# Main.net
KiCad netlist of a schematic drawn in Altium Designer
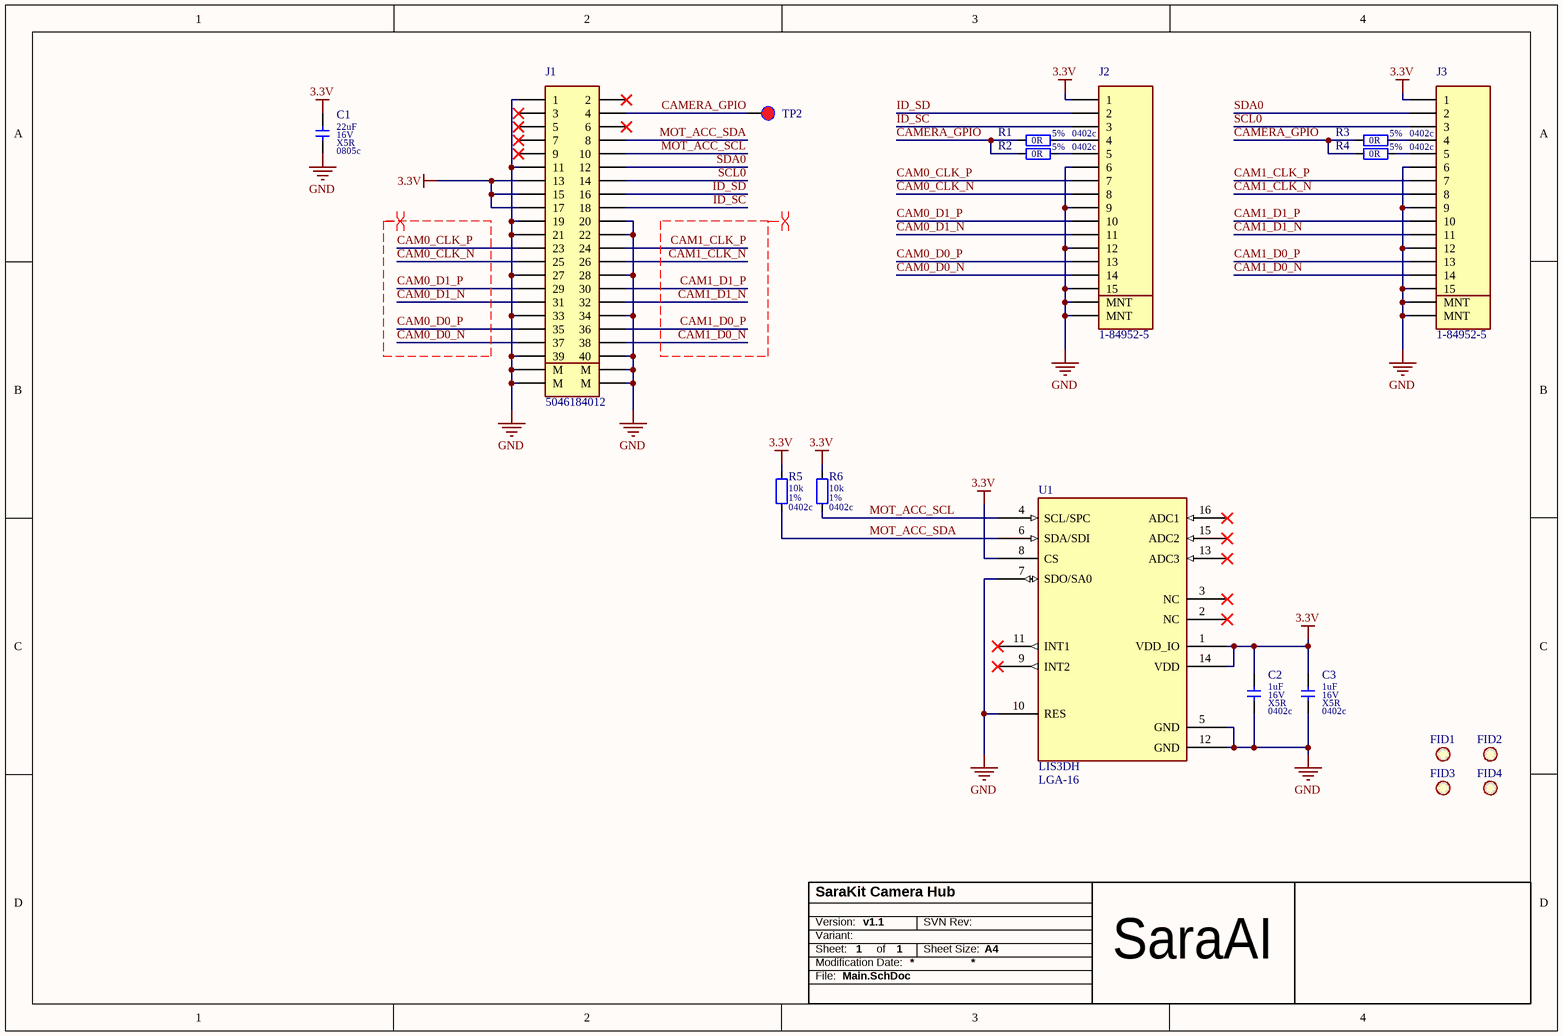
[diagram p0: Main.SchDoc]

(export (version "E")
  (design (tool "Eeschema 10.0.6"))
  (components
    (comp (ref "C1")
      (value "CL21A226MOQNNNE")
      (footprint "CAPC2013X145L")
      (description "SMT 0805c 22uF 16V 20% X5R 1.6MHz 85'C")
      (fields
        (field (name "11 PARAMETER 4") "X5R")
        (field (name "07 PACKAGE") "0805c")
        (field (name "08 PARAMETER 1") "22uF")
        (field (name "09 PARAMETER 2") "16V")
      )
      (libsource (lib "MS_Altium_Lib") (part "CAPACITOR"))
    )
    (comp (ref "C2")
      (value "CL05A105KO5NNNC")
      (footprint "CAPC1005X60L")
      (description "SMT 0402c 1uF 16V 10% X5R 11.9MHz 85'C")
      (fields
        (field (name "11 PARAMETER 4") "X5R")
        (field (name "07 PACKAGE") "0402c")
        (field (name "08 PARAMETER 1") "1uF")
        (field (name "09 PARAMETER 2") "16V")
      )
      (libsource (lib "MS_Altium_Lib") (part "CAPACITOR"))
    )
    (comp (ref "C3")
      (value "CL05A105KO5NNNC")
      (footprint "CAPC1005X60L")
      (description "SMT 0402c 1uF 16V 10% X5R 11.9MHz 85'C")
      (fields
        (field (name "11 PARAMETER 4") "X5R")
        (field (name "07 PACKAGE") "0402c")
        (field (name "08 PARAMETER 1") "1uF")
        (field (name "09 PARAMETER 2") "16V")
      )
      (libsource (lib "MS_Altium_Lib") (part "CAPACITOR"))
    )
    (comp (ref "FID1")
      (value "FIDUCIAL")
      (footprint "FIDUCIAL 2MM")
      (libsource (lib "MS_Altium_Lib") (part "FIDUCIAL"))
    )
    (comp (ref "FID2")
      (value "FIDUCIAL")
      (footprint "FIDUCIAL 2MM")
      (libsource (lib "MS_Altium_Lib") (part "FIDUCIAL"))
    )
    (comp (ref "FID3")
      (value "FIDUCIAL")
      (footprint "FIDUCIAL 2MM")
      (libsource (lib "MS_Altium_Lib") (part "FIDUCIAL"))
    )
    (comp (ref "FID4")
      (value "FIDUCIAL")
      (footprint "FIDUCIAL 2MM")
      (libsource (lib "MS_Altium_Lib") (part "FIDUCIAL"))
    )
    (comp (ref "J1")
      (value "5046184012")
      (footprint "MOLEX 5046184012")
      (description "SMT 2x20 0.35mm Straight 50V 0.3A")
      (fields (field (name "02 MPN") "5046184012"))
      (libsource (lib "MS_Altium_Lib") (part "CONNECTOR 2X22 4MNT ODDEVEN"))
    )
    (comp (ref "J2")
      (value "1-84952-5")
      (footprint "TE 1-84952-5")
      (description "SMT 1x15 1mm Bottom Contact Right Angle 200VAC 1A")
      (fields (field (name "02 MPN") "1-84952-5"))
      (libsource (lib "MS_Altium_Lib") (part "CONNECTOR 1X15 2MNT"))
    )
    (comp (ref "J3")
      (value "1-84952-5")
      (footprint "TE 1-84952-5")
      (description "SMT 1x15 1mm Bottom Contact Right Angle 200VAC 1A")
      (fields (field (name "02 MPN") "1-84952-5"))
      (libsource (lib "MS_Altium_Lib") (part "CONNECTOR 1X15 2MNT"))
    )
    (comp (ref "R1")
      (value "RC0402JR-070RL")
      (footprint "RESC1005X40L")
      (description "SMT 0402c 0R 5% 62.5mW 200ppm/K 50V")
      (fields
        (field (name "07 PACKAGE") "0402c")
        (field (name "09 PARAMETER 2") "5%")
        (field (name "08 PARAMETER 1") "0R")
      )
      (libsource (lib "MS_Altium_Lib") (part "RESISTOR"))
    )
    (comp (ref "R2")
      (value "RC0402JR-070RL")
      (footprint "RESC1005X40L")
      (description "SMT 0402c 0R 5% 62.5mW 200ppm/K 50V")
      (fields
        (field (name "07 PACKAGE") "0402c")
        (field (name "09 PARAMETER 2") "5%")
        (field (name "08 PARAMETER 1") "0R")
      )
      (libsource (lib "MS_Altium_Lib") (part "RESISTOR"))
    )
    (comp (ref "R3")
      (value "RC0402JR-070RL")
      (footprint "RESC1005X40L")
      (description "SMT 0402c 0R 5% 62.5mW 200ppm/K 50V")
      (fields
        (field (name "07 PACKAGE") "0402c")
        (field (name "09 PARAMETER 2") "5%")
        (field (name "08 PARAMETER 1") "0R")
      )
      (libsource (lib "MS_Altium_Lib") (part "RESISTOR"))
    )
    (comp (ref "R4")
      (value "RC0402JR-070RL")
      (footprint "RESC1005X40L")
      (description "SMT 0402c 0R 5% 62.5mW 200ppm/K 50V")
      (fields
        (field (name "07 PACKAGE") "0402c")
        (field (name "09 PARAMETER 2") "5%")
        (field (name "08 PARAMETER 1") "0R")
      )
      (libsource (lib "MS_Altium_Lib") (part "RESISTOR"))
    )
    (comp (ref "R5")
      (value "RC0402FR-0710KL")
      (footprint "RESC1005X40L")
      (description "SMT 0402c 10k 1% 62.5mW 100ppm/K 50V")
      (fields
        (field (name "07 PACKAGE") "0402c")
        (field (name "09 PARAMETER 2") "1%")
        (field (name "08 PARAMETER 1") "10k")
      )
      (libsource (lib "") (part "RESISTOR_1"))
    )
    (comp (ref "R6")
      (value "RC0402FR-0710KL")
      (footprint "RESC1005X40L")
      (description "SMT 0402c 10k 1% 62.5mW 100ppm/K 50V")
      (fields
        (field (name "07 PACKAGE") "0402c")
        (field (name "09 PARAMETER 2") "1%")
        (field (name "08 PARAMETER 1") "10k")
      )
      (libsource (lib "") (part "RESISTOR_1"))
    )
    (comp (ref "TP2")
      (value "TESTPAD")
      (footprint "TP 1.5mm")
      (libsource (lib "MS_Altium_Lib") (part "TESTPAD"))
    )
    (comp (ref "U1")
      (value "LIS3DH")
      (footprint "LGA16R50P5X3_300X300X100")
      (description "SMT LGA-16 ACCELEROMETER 1.71V - 3.6V +/- 16g")
      (fields (field (name "02 MPN") "LIS3DH") (field (name "07 PACKAGE") "LGA-16"))
      (libsource (lib "MS_Altium_Lib") (part "LIS3DH"))
    )
  )
  (nets
    (net (code "2") (name "/CAM0_CLK_N") (class "Default")
      (node (ref "J1") (pin "25") (pinfunction "25_25") (pintype "passive"))
      (node (ref "J2") (pin "8") (pinfunction "8_8") (pintype "passive"))
    )
    (net (code "3") (name "/CAM0_CLK_P") (class "Default")
      (node (ref "J1") (pin "23") (pinfunction "23_23") (pintype "passive"))
      (node (ref "J2") (pin "7") (pinfunction "7_7") (pintype "passive"))
    )
    (net (code "4") (name "/CAM0_D0_N") (class "Default")
      (node (ref "J1") (pin "37") (pinfunction "37_37") (pintype "passive"))
      (node (ref "J2") (pin "14") (pinfunction "14_14") (pintype "passive"))
    )
    (net (code "5") (name "/CAM0_D0_P") (class "Default")
      (node (ref "J1") (pin "35") (pinfunction "35_35") (pintype "passive"))
      (node (ref "J2") (pin "13") (pinfunction "13_13") (pintype "passive"))
    )
    (net (code "6") (name "/CAM0_D1_N") (class "Default")
      (node (ref "J1") (pin "31") (pinfunction "31_31") (pintype "passive"))
      (node (ref "J2") (pin "11") (pinfunction "11_11") (pintype "passive"))
    )
    (net (code "7") (name "/CAM0_D1_P") (class "Default")
      (node (ref "J1") (pin "29") (pinfunction "29_29") (pintype "passive"))
      (node (ref "J2") (pin "10") (pinfunction "10_10") (pintype "passive"))
    )
    (net (code "8") (name "/CAM1_CLK_N") (class "Default")
      (node (ref "J1") (pin "26") (pinfunction "26_26") (pintype "passive"))
      (node (ref "J3") (pin "8") (pinfunction "8_8") (pintype "passive"))
    )
    (net (code "9") (name "/CAM1_CLK_P") (class "Default")
      (node (ref "J1") (pin "24") (pinfunction "24_24") (pintype "passive"))
      (node (ref "J3") (pin "7") (pinfunction "7_7") (pintype "passive"))
    )
    (net (code "10") (name "/CAM1_D0_N") (class "Default")
      (node (ref "J1") (pin "38") (pinfunction "38_38") (pintype "passive"))
      (node (ref "J3") (pin "14") (pinfunction "14_14") (pintype "passive"))
    )
    (net (code "11") (name "/CAM1_D0_P") (class "Default")
      (node (ref "J1") (pin "36") (pinfunction "36_36") (pintype "passive"))
      (node (ref "J3") (pin "13") (pinfunction "13_13") (pintype "passive"))
    )
    (net (code "12") (name "/CAM1_D1_N") (class "Default")
      (node (ref "J1") (pin "32") (pinfunction "32_32") (pintype "passive"))
      (node (ref "J3") (pin "11") (pinfunction "11_11") (pintype "passive"))
    )
    (net (code "13") (name "/CAM1_D1_P") (class "Default")
      (node (ref "J1") (pin "30") (pinfunction "30_30") (pintype "passive"))
      (node (ref "J3") (pin "10") (pinfunction "10_10") (pintype "passive"))
    )
    (net (code "14") (name "/CAMERA_GPIO") (class "Default")
      (node (ref "J1") (pin "4") (pinfunction "4_4") (pintype "passive"))
      (node (ref "R1") (pin "1") (pinfunction "1_1") (pintype "passive"))
      (node (ref "R2") (pin "1") (pinfunction "1_1") (pintype "passive"))
      (node (ref "R3") (pin "1") (pinfunction "1_1") (pintype "passive"))
      (node (ref "R4") (pin "1") (pinfunction "1_1") (pintype "passive"))
      (node (ref "TP2") (pin "1") (pinfunction "1_1") (pintype "passive"))
    )
    (net (code "15") (name "/ID_SC") (class "Default")
      (node (ref "J1") (pin "18") (pinfunction "18_18") (pintype "passive"))
      (node (ref "J2") (pin "3") (pinfunction "3_3") (pintype "passive"))
    )
    (net (code "16") (name "/ID_SD") (class "Default")
      (node (ref "J1") (pin "16") (pinfunction "16_16") (pintype "passive"))
      (node (ref "J2") (pin "2") (pinfunction "2_2") (pintype "passive"))
    )
    (net (code "17") (name "/MOT_ACC_SCL") (class "Default")
      (node (ref "J1") (pin "10") (pinfunction "10_10") (pintype "passive"))
      (node (ref "R6") (pin "1") (pinfunction "1_1") (pintype "passive"))
      (node (ref "U1") (pin "4") (pinfunction "SCL/SPC_4") (pintype "input"))
    )
    (net (code "18") (name "/MOT_ACC_SDA") (class "Default")
      (node (ref "J1") (pin "8") (pinfunction "8_8") (pintype "passive"))
      (node (ref "R5") (pin "1") (pinfunction "1_1") (pintype "passive"))
      (node (ref "U1") (pin "6") (pinfunction "SDA/SDI_6") (pintype "input"))
    )
    (net (code "19") (name "/SCL0") (class "Default")
      (node (ref "J1") (pin "14") (pinfunction "14_14") (pintype "passive"))
      (node (ref "J3") (pin "3") (pinfunction "3_3") (pintype "passive"))
    )
    (net (code "20") (name "/SDA0") (class "Default")
      (node (ref "J1") (pin "12") (pinfunction "12_12") (pintype "passive"))
      (node (ref "J3") (pin "2") (pinfunction "2_2") (pintype "passive"))
    )
    (net (code "21") (name "3.3V") (class "Default")
      (node (ref "C1") (pin "2") (pinfunction "2_2") (pintype "passive"))
      (node (ref "C2") (pin "2") (pinfunction "2_2") (pintype "passive"))
      (node (ref "C3") (pin "2") (pinfunction "2_2") (pintype "passive"))
      (node (ref "J1") (pin "13") (pinfunction "13_13") (pintype "passive"))
      (node (ref "J1") (pin "15") (pinfunction "15_15") (pintype "passive"))
      (node (ref "J1") (pin "17") (pinfunction "17_17") (pintype "passive"))
      (node (ref "J2") (pin "1") (pinfunction "1_1") (pintype "passive"))
      (node (ref "J3") (pin "1") (pinfunction "1_1") (pintype "passive"))
      (node (ref "R5") (pin "2") (pinfunction "2_2") (pintype "passive"))
      (node (ref "R6") (pin "2") (pinfunction "2_2") (pintype "passive"))
      (node (ref "U1") (pin "1") (pinfunction "VDD_IO_1") (pintype "power_in"))
      (node (ref "U1") (pin "14") (pinfunction "VDD_14") (pintype "power_in"))
      (node (ref "U1") (pin "8") (pinfunction "CS_8") (pintype "passive"))
    )
    (net (code "22") (name "GND") (class "Default")
      (node (ref "C1") (pin "1") (pinfunction "1_1") (pintype "passive"))
      (node (ref "C2") (pin "1") (pinfunction "1_1") (pintype "passive"))
      (node (ref "C3") (pin "1") (pinfunction "1_1") (pintype "passive"))
      (node (ref "J1") (pin "1") (pinfunction "1_1") (pintype "passive"))
      (node (ref "J1") (pin "11") (pinfunction "11_11") (pintype "passive"))
      (node (ref "J1") (pin "19") (pinfunction "19_19") (pintype "passive"))
      (node (ref "J1") (pin "20") (pinfunction "20_20") (pintype "passive"))
      (node (ref "J1") (pin "21") (pinfunction "21_21") (pintype "passive"))
      (node (ref "J1") (pin "22") (pinfunction "22_22") (pintype "passive"))
      (node (ref "J1") (pin "27") (pinfunction "27_27") (pintype "passive"))
      (node (ref "J1") (pin "28") (pinfunction "28_28") (pintype "passive"))
      (node (ref "J1") (pin "33") (pinfunction "33_33") (pintype "passive"))
      (node (ref "J1") (pin "34") (pinfunction "34_34") (pintype "passive"))
      (node (ref "J1") (pin "39") (pinfunction "39_39") (pintype "passive"))
      (node (ref "J1") (pin "40") (pinfunction "40_40") (pintype "passive"))
      (node (ref "J1") (pin "MNT1") (pinfunction "M_MNT1") (pintype "passive"))
      (node (ref "J1") (pin "MNT2") (pinfunction "M_MNT2") (pintype "passive"))
      (node (ref "J1") (pin "MNT3") (pinfunction "M_MNT3") (pintype "passive"))
      (node (ref "J1") (pin "MNT4") (pinfunction "M_MNT4") (pintype "passive"))
      (node (ref "J2") (pin "12") (pinfunction "12_12") (pintype "passive"))
      (node (ref "J2") (pin "15") (pinfunction "15_15") (pintype "passive"))
      (node (ref "J2") (pin "6") (pinfunction "6_6") (pintype "passive"))
      (node (ref "J2") (pin "9") (pinfunction "9_9") (pintype "passive"))
      (node (ref "J2") (pin "MNT1") (pinfunction "MNT_MNT1") (pintype "passive"))
      (node (ref "J2") (pin "MNT2") (pinfunction "MNT_MNT2") (pintype "passive"))
      (node (ref "J3") (pin "12") (pinfunction "12_12") (pintype "passive"))
      (node (ref "J3") (pin "15") (pinfunction "15_15") (pintype "passive"))
      (node (ref "J3") (pin "6") (pinfunction "6_6") (pintype "passive"))
      (node (ref "J3") (pin "9") (pinfunction "9_9") (pintype "passive"))
      (node (ref "J3") (pin "MNT1") (pinfunction "MNT_MNT1") (pintype "passive"))
      (node (ref "J3") (pin "MNT2") (pinfunction "MNT_MNT2") (pintype "passive"))
      (node (ref "U1") (pin "10") (pinfunction "RES_10") (pintype "passive"))
      (node (ref "U1") (pin "12") (pinfunction "GND_12") (pintype "power_in"))
      (node (ref "U1") (pin "5") (pinfunction "GND_5") (pintype "power_in"))
      (node (ref "U1") (pin "7") (pinfunction "SDO/SA0_7") (pintype "bidirectional"))
    )
    (net (code "23") (name "Net-(J2-Pad4)") (class "Default")
      (node (ref "J2") (pin "4") (pinfunction "4_4") (pintype "passive"))
      (node (ref "R1") (pin "2") (pinfunction "2_2") (pintype "passive"))
    )
    (net (code "24") (name "Net-(J2-Pad5)") (class "Default")
      (node (ref "J2") (pin "5") (pinfunction "5_5") (pintype "passive"))
      (node (ref "R2") (pin "2") (pinfunction "2_2") (pintype "passive"))
    )
    (net (code "25") (name "Net-(J3-Pad4)") (class "Default")
      (node (ref "J3") (pin "4") (pinfunction "4_4") (pintype "passive"))
      (node (ref "R3") (pin "2") (pinfunction "2_2") (pintype "passive"))
    )
    (net (code "26") (name "Net-(J3-Pad5)") (class "Default")
      (node (ref "J3") (pin "5") (pinfunction "5_5") (pintype "passive"))
      (node (ref "R4") (pin "2") (pinfunction "2_2") (pintype "passive"))
    )
    (net (code "27") (name "unconnected-(J1-Pad2)") (class "Default")
      (node (ref "J1") (pin "2") (pinfunction "2_2") (pintype "passive+no_connect"))
    )
    (net (code "28") (name "unconnected-(J1-Pad3)") (class "Default")
      (node (ref "J1") (pin "3") (pinfunction "3_3") (pintype "passive+no_connect"))
    )
    (net (code "29") (name "unconnected-(J1-Pad5)") (class "Default")
      (node (ref "J1") (pin "5") (pinfunction "5_5") (pintype "passive+no_connect"))
    )
    (net (code "30") (name "unconnected-(J1-Pad6)") (class "Default")
      (node (ref "J1") (pin "6") (pinfunction "6_6") (pintype "passive+no_connect"))
    )
    (net (code "31") (name "unconnected-(J1-Pad7)") (class "Default")
      (node (ref "J1") (pin "7") (pinfunction "7_7") (pintype "passive+no_connect"))
    )
    (net (code "32") (name "unconnected-(J1-Pad9)") (class "Default")
      (node (ref "J1") (pin "9") (pinfunction "9_9") (pintype "passive+no_connect"))
    )
    (net (code "33") (name "unconnected-(U1-ADC1-Pad16)") (class "Default")
      (node (ref "U1") (pin "16") (pinfunction "ADC1_16") (pintype "input+no_connect"))
    )
    (net (code "34") (name "unconnected-(U1-ADC2-Pad15)") (class "Default")
      (node (ref "U1") (pin "15") (pinfunction "ADC2_15") (pintype "input+no_connect"))
    )
    (net (code "35") (name "unconnected-(U1-ADC3-Pad13)") (class "Default")
      (node (ref "U1") (pin "13") (pinfunction "ADC3_13") (pintype "input+no_connect"))
    )
    (net (code "36") (name "unconnected-(U1-INT1-Pad11)") (class "Default")
      (node (ref "U1") (pin "11") (pinfunction "INT1_11") (pintype "output+no_connect"))
    )
    (net (code "37") (name "unconnected-(U1-INT2-Pad9)") (class "Default")
      (node (ref "U1") (pin "9") (pinfunction "INT2_9") (pintype "output+no_connect"))
    )
    (net (code "38") (name "unconnected-(U1-NC-Pad2)") (class "Default")
      (node (ref "U1") (pin "2") (pinfunction "NC_2") (pintype "passive+no_connect"))
    )
    (net (code "39") (name "unconnected-(U1-NC-Pad3)") (class "Default")
      (node (ref "U1") (pin "3") (pinfunction "NC_3") (pintype "passive+no_connect"))
    )
  )
)
